# adapter.net
KiCad netlist of a schematic drawn in EAGLE
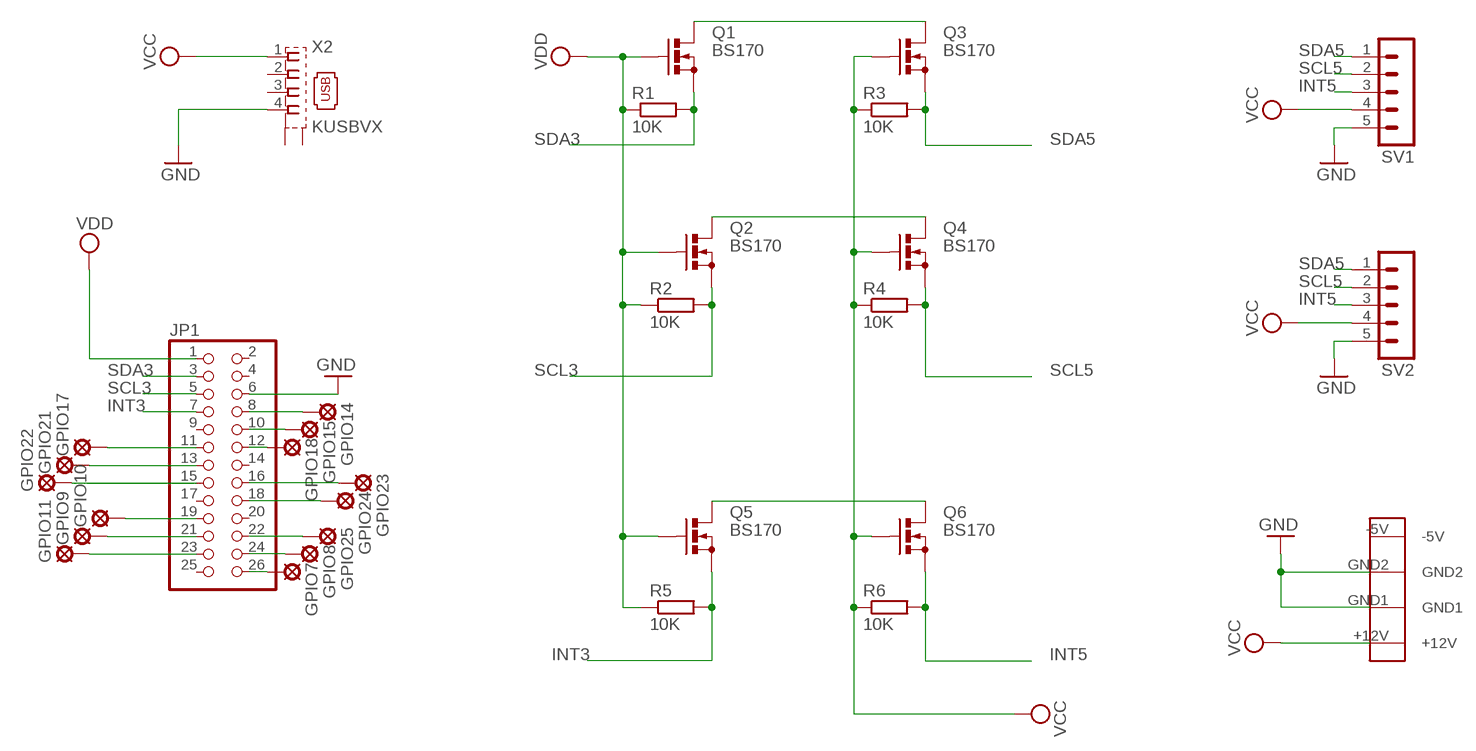
[diagram p0: schematic, sheet 1]

(export (version "E")
  (design (tool "Eeschema 10.0.6"))
  (components
    (comp (ref "GPIO7")
      (value "LSP10")
      (footprint "eagle-import:LSP10")
      (libsource (lib "eagle-import") (part "LSP10"))
    )
    (comp (ref "GPIO8")
      (value "LSP10")
      (footprint "eagle-import:LSP10")
      (libsource (lib "eagle-import") (part "LSP10"))
    )
    (comp (ref "GPIO9")
      (value "LSP10")
      (footprint "eagle-import:LSP10")
      (libsource (lib "eagle-import") (part "LSP10"))
    )
    (comp (ref "GPIO10")
      (value "LSP10")
      (footprint "eagle-import:LSP10")
      (libsource (lib "eagle-import") (part "LSP10"))
    )
    (comp (ref "GPIO11")
      (value "LSP10")
      (footprint "eagle-import:LSP10")
      (libsource (lib "eagle-import") (part "LSP10"))
    )
    (comp (ref "GPIO14")
      (value "LSP10")
      (footprint "eagle-import:LSP10")
      (libsource (lib "eagle-import") (part "LSP10"))
    )
    (comp (ref "GPIO15")
      (value "LSP10")
      (footprint "eagle-import:LSP10")
      (libsource (lib "eagle-import") (part "LSP10"))
    )
    (comp (ref "GPIO17")
      (value "GPIO17")
      (footprint "eagle-import:LSP10")
      (libsource (lib "eagle-import") (part "LSP10"))
    )
    (comp (ref "GPIO18")
      (value "LSP10")
      (footprint "eagle-import:LSP10")
      (libsource (lib "eagle-import") (part "LSP10"))
    )
    (comp (ref "GPIO21")
      (value "LSP10")
      (footprint "eagle-import:LSP10")
      (libsource (lib "eagle-import") (part "LSP10"))
    )
    (comp (ref "GPIO22")
      (value "LSP10")
      (footprint "eagle-import:LSP10")
      (libsource (lib "eagle-import") (part "LSP10"))
    )
    (comp (ref "GPIO23")
      (value "LSP10")
      (footprint "eagle-import:LSP10")
      (libsource (lib "eagle-import") (part "LSP10"))
    )
    (comp (ref "GPIO24")
      (value "LSP10")
      (footprint "eagle-import:LSP10")
      (libsource (lib "eagle-import") (part "LSP10"))
    )
    (comp (ref "GPIO25")
      (value "LSP10")
      (footprint "eagle-import:LSP10")
      (libsource (lib "eagle-import") (part "LSP10"))
    )
    (comp (ref "JP1")
      (value "PINHD-2X13")
      (footprint "eagle-import:2X13")
      (libsource (lib "eagle-import") (part "PINHD-2X13"))
    )
    (comp (ref "Q1")
      (value "BS170")
      (footprint "eagle-import:SOT54E")
      (libsource (lib "eagle-import") (part "BS170"))
    )
    (comp (ref "Q2")
      (value "BS170")
      (footprint "eagle-import:SOT54E")
      (libsource (lib "eagle-import") (part "BS170"))
    )
    (comp (ref "Q3")
      (value "BS170")
      (footprint "eagle-import:SOT54E")
      (libsource (lib "eagle-import") (part "BS170"))
    )
    (comp (ref "Q4")
      (value "BS170")
      (footprint "eagle-import:SOT54E")
      (libsource (lib "eagle-import") (part "BS170"))
    )
    (comp (ref "Q5")
      (value "BS170")
      (footprint "eagle-import:SOT54E")
      (libsource (lib "eagle-import") (part "BS170"))
    )
    (comp (ref "Q6")
      (value "BS170")
      (footprint "eagle-import:SOT54E")
      (libsource (lib "eagle-import") (part "BS170"))
    )
    (comp (ref "R1")
      (value "10K")
      (footprint "eagle-import:0207_2V")
      (libsource (lib "eagle-import") (part "R-EU_0207/2V"))
    )
    (comp (ref "R2")
      (value "10K")
      (footprint "eagle-import:0207_2V")
      (libsource (lib "eagle-import") (part "R-EU_0207/2V"))
    )
    (comp (ref "R3")
      (value "10K")
      (footprint "eagle-import:0207_2V")
      (libsource (lib "eagle-import") (part "R-EU_0207/2V"))
    )
    (comp (ref "R4")
      (value "10K")
      (footprint "eagle-import:0207_2V")
      (libsource (lib "eagle-import") (part "R-EU_0207/2V"))
    )
    (comp (ref "R5")
      (value "10K")
      (footprint "eagle-import:0207_2V")
      (libsource (lib "eagle-import") (part "R-EU_0207/2V"))
    )
    (comp (ref "R6")
      (value "10K")
      (footprint "eagle-import:0207_2V")
      (libsource (lib "eagle-import") (part "R-EU_0207/2V"))
    )
    (comp (ref "SV1")
      (value "MA05-1")
      (footprint "eagle-import:MA05-1")
      (libsource (lib "eagle-import") (part "MA05-1"))
    )
    (comp (ref "SV2")
      (value "MA05-1")
      (footprint "eagle-import:MA05-1")
      (libsource (lib "eagle-import") (part "MA05-1"))
    )
    (comp (ref "U$1")
      (value "PSW_5")
      (footprint "eagle-import:PSW_5")
      (libsource (lib "eagle-import") (part "PSW_5"))
    )
    (comp (ref "X2")
      (value "KUSBVX")
      (footprint "eagle-import:KUSBVX")
      (libsource (lib "eagle-import") (part "KUSBVX"))
    )
  )
  (nets
    (net (code "1") (name "/INT3") (class "Default")
      (node (ref "JP1") (pin "7") (pinfunction "7_7") (pintype "passive"))
      (node (ref "Q5") (pin "S") (pinfunction "S_S") (pintype "passive"))
      (node (ref "R5") (pin "2") (pinfunction "2_2") (pintype "passive"))
    )
    (net (code "2") (name "/INT5") (class "Default")
      (node (ref "Q6") (pin "S") (pinfunction "S_S") (pintype "passive"))
      (node (ref "R6") (pin "2") (pinfunction "2_2") (pintype "passive"))
      (node (ref "SV1") (pin "3") (pinfunction "3_3") (pintype "passive"))
      (node (ref "SV2") (pin "3") (pinfunction "3_3") (pintype "passive"))
    )
    (net (code "3") (name "/SCL3") (class "Default")
      (node (ref "JP1") (pin "5") (pinfunction "5_5") (pintype "passive"))
      (node (ref "Q2") (pin "S") (pinfunction "S_S") (pintype "passive"))
      (node (ref "R2") (pin "2") (pinfunction "2_2") (pintype "passive"))
    )
    (net (code "4") (name "/SCL5") (class "Default")
      (node (ref "Q4") (pin "S") (pinfunction "S_S") (pintype "passive"))
      (node (ref "R4") (pin "2") (pinfunction "2_2") (pintype "passive"))
      (node (ref "SV1") (pin "2") (pinfunction "2_2") (pintype "passive"))
      (node (ref "SV2") (pin "2") (pinfunction "2_2") (pintype "passive"))
    )
    (net (code "5") (name "/SDA3") (class "Default")
      (node (ref "JP1") (pin "3") (pinfunction "3_3") (pintype "passive"))
      (node (ref "Q1") (pin "S") (pinfunction "S_S") (pintype "passive"))
      (node (ref "R1") (pin "2") (pinfunction "2_2") (pintype "passive"))
    )
    (net (code "6") (name "/SDA5") (class "Default")
      (node (ref "Q3") (pin "S") (pinfunction "S_S") (pintype "passive"))
      (node (ref "R3") (pin "2") (pinfunction "2_2") (pintype "passive"))
      (node (ref "SV1") (pin "1") (pinfunction "1_1") (pintype "passive"))
      (node (ref "SV2") (pin "1") (pinfunction "1_1") (pintype "passive"))
    )
    (net (code "7") (name "GND") (class "Default")
      (node (ref "JP1") (pin "6") (pinfunction "6_6") (pintype "passive"))
      (node (ref "SV1") (pin "5") (pinfunction "5_5") (pintype "passive"))
      (node (ref "SV2") (pin "5") (pinfunction "5_5") (pintype "passive"))
      (node (ref "U$1") (pin "GND1") (pinfunction "GND1_GND1") (pintype "bidirectional"))
      (node (ref "U$1") (pin "GND2") (pinfunction "GND2_GND2") (pintype "bidirectional"))
      (node (ref "X2") (pin "4") (pinfunction "4_4") (pintype "passive"))
    )
    (net (code "8") (name "Net-(GPIO7-PadMP)") (class "Default")
      (node (ref "GPIO7") (pin "MP") (pinfunction "MP_MP") (pintype "passive"))
      (node (ref "JP1") (pin "26") (pinfunction "26_26") (pintype "passive"))
    )
    (net (code "9") (name "Net-(GPIO8-PadMP)") (class "Default")
      (node (ref "GPIO8") (pin "MP") (pinfunction "MP_MP") (pintype "passive"))
      (node (ref "JP1") (pin "24") (pinfunction "24_24") (pintype "passive"))
    )
    (net (code "10") (name "Net-(GPIO9-PadMP)") (class "Default")
      (node (ref "GPIO9") (pin "MP") (pinfunction "MP_MP") (pintype "passive"))
      (node (ref "JP1") (pin "21") (pinfunction "21_21") (pintype "passive"))
    )
    (net (code "11") (name "Net-(GPIO10-PadMP)") (class "Default")
      (node (ref "GPIO10") (pin "MP") (pinfunction "MP_MP") (pintype "passive"))
      (node (ref "JP1") (pin "19") (pinfunction "19_19") (pintype "passive"))
    )
    (net (code "12") (name "Net-(GPIO11-PadMP)") (class "Default")
      (node (ref "GPIO11") (pin "MP") (pinfunction "MP_MP") (pintype "passive"))
      (node (ref "JP1") (pin "23") (pinfunction "23_23") (pintype "passive"))
    )
    (net (code "13") (name "Net-(GPIO14-PadMP)") (class "Default")
      (node (ref "GPIO14") (pin "MP") (pinfunction "MP_MP") (pintype "passive"))
      (node (ref "JP1") (pin "8") (pinfunction "8_8") (pintype "passive"))
    )
    (net (code "14") (name "Net-(GPIO15-PadMP)") (class "Default")
      (node (ref "GPIO15") (pin "MP") (pinfunction "MP_MP") (pintype "passive"))
      (node (ref "JP1") (pin "10") (pinfunction "10_10") (pintype "passive"))
    )
    (net (code "15") (name "Net-(GPIO17-PadMP)") (class "Default")
      (node (ref "GPIO17") (pin "MP") (pinfunction "MP_MP") (pintype "passive"))
      (node (ref "JP1") (pin "11") (pinfunction "11_11") (pintype "passive"))
    )
    (net (code "16") (name "Net-(GPIO18-PadMP)") (class "Default")
      (node (ref "GPIO18") (pin "MP") (pinfunction "MP_MP") (pintype "passive"))
      (node (ref "JP1") (pin "12") (pinfunction "12_12") (pintype "passive"))
    )
    (net (code "17") (name "Net-(GPIO21-PadMP)") (class "Default")
      (node (ref "GPIO21") (pin "MP") (pinfunction "MP_MP") (pintype "passive"))
      (node (ref "JP1") (pin "13") (pinfunction "13_13") (pintype "passive"))
    )
    (net (code "18") (name "Net-(GPIO22-PadMP)") (class "Default")
      (node (ref "GPIO22") (pin "MP") (pinfunction "MP_MP") (pintype "passive"))
      (node (ref "JP1") (pin "15") (pinfunction "15_15") (pintype "passive"))
    )
    (net (code "19") (name "Net-(GPIO23-PadMP)") (class "Default")
      (node (ref "GPIO23") (pin "MP") (pinfunction "MP_MP") (pintype "passive"))
      (node (ref "JP1") (pin "16") (pinfunction "16_16") (pintype "passive"))
    )
    (net (code "20") (name "Net-(GPIO24-PadMP)") (class "Default")
      (node (ref "GPIO24") (pin "MP") (pinfunction "MP_MP") (pintype "passive"))
      (node (ref "JP1") (pin "18") (pinfunction "18_18") (pintype "passive"))
    )
    (net (code "21") (name "Net-(GPIO25-PadMP)") (class "Default")
      (node (ref "GPIO25") (pin "MP") (pinfunction "MP_MP") (pintype "passive"))
      (node (ref "JP1") (pin "22") (pinfunction "22_22") (pintype "passive"))
    )
    (net (code "22") (name "Net-(Q1-PadD)") (class "Default")
      (node (ref "Q1") (pin "D") (pinfunction "D_D") (pintype "passive"))
      (node (ref "Q3") (pin "D") (pinfunction "D_D") (pintype "passive"))
    )
    (net (code "23") (name "Net-(Q2-PadD)") (class "Default")
      (node (ref "Q2") (pin "D") (pinfunction "D_D") (pintype "passive"))
      (node (ref "Q4") (pin "D") (pinfunction "D_D") (pintype "passive"))
    )
    (net (code "24") (name "Net-(Q5-PadD)") (class "Default")
      (node (ref "Q5") (pin "D") (pinfunction "D_D") (pintype "passive"))
      (node (ref "Q6") (pin "D") (pinfunction "D_D") (pintype "passive"))
    )
    (net (code "25") (name "VCC") (class "Default")
      (node (ref "Q3") (pin "G") (pinfunction "G_G") (pintype "passive"))
      (node (ref "Q4") (pin "G") (pinfunction "G_G") (pintype "passive"))
      (node (ref "Q6") (pin "G") (pinfunction "G_G") (pintype "passive"))
      (node (ref "R3") (pin "1") (pinfunction "1_1") (pintype "passive"))
      (node (ref "R4") (pin "1") (pinfunction "1_1") (pintype "passive"))
      (node (ref "R6") (pin "1") (pinfunction "1_1") (pintype "passive"))
      (node (ref "SV1") (pin "4") (pinfunction "4_4") (pintype "passive"))
      (node (ref "SV2") (pin "4") (pinfunction "4_4") (pintype "passive"))
      (node (ref "U$1") (pin "+12V") (pinfunction "+12V_+12V") (pintype "bidirectional"))
      (node (ref "X2") (pin "1") (pinfunction "1_1") (pintype "passive"))
    )
    (net (code "26") (name "VDD") (class "Default")
      (node (ref "JP1") (pin "1") (pinfunction "1_1") (pintype "passive"))
      (node (ref "Q1") (pin "G") (pinfunction "G_G") (pintype "passive"))
      (node (ref "Q2") (pin "G") (pinfunction "G_G") (pintype "passive"))
      (node (ref "Q5") (pin "G") (pinfunction "G_G") (pintype "passive"))
      (node (ref "R1") (pin "1") (pinfunction "1_1") (pintype "passive"))
      (node (ref "R2") (pin "1") (pinfunction "1_1") (pintype "passive"))
      (node (ref "R5") (pin "1") (pinfunction "1_1") (pintype "passive"))
    )
    (net (code "27") (name "unconnected-(JP1-Pad2)") (class "Default")
      (node (ref "JP1") (pin "2") (pinfunction "2_2") (pintype "passive"))
    )
    (net (code "28") (name "unconnected-(JP1-Pad4)") (class "Default")
      (node (ref "JP1") (pin "4") (pinfunction "4_4") (pintype "passive"))
    )
    (net (code "29") (name "unconnected-(JP1-Pad9)") (class "Default")
      (node (ref "JP1") (pin "9") (pinfunction "9_9") (pintype "passive"))
    )
    (net (code "30") (name "unconnected-(JP1-Pad14)") (class "Default")
      (node (ref "JP1") (pin "14") (pinfunction "14_14") (pintype "passive"))
    )
    (net (code "31") (name "unconnected-(JP1-Pad17)") (class "Default")
      (node (ref "JP1") (pin "17") (pinfunction "17_17") (pintype "passive"))
    )
    (net (code "32") (name "unconnected-(JP1-Pad20)") (class "Default")
      (node (ref "JP1") (pin "20") (pinfunction "20_20") (pintype "passive"))
    )
    (net (code "33") (name "unconnected-(JP1-Pad25)") (class "Default")
      (node (ref "JP1") (pin "25") (pinfunction "25_25") (pintype "passive"))
    )
    (net (code "34") (name "unconnected-(U$1-Pad-5V)") (class "Default")
      (node (ref "U$1") (pin "-5V") (pinfunction "-5V_-5V") (pintype "bidirectional"))
    )
    (net (code "35") (name "unconnected-(X2-Pad2)") (class "Default")
      (node (ref "X2") (pin "2") (pinfunction "2_2") (pintype "passive"))
    )
    (net (code "36") (name "unconnected-(X2-Pad3)") (class "Default")
      (node (ref "X2") (pin "3") (pinfunction "3_3") (pintype "passive"))
    )
    (net (code "37") (name "unconnected-(X2-S1-PadM1)") (class "Default")
      (node (ref "X2") (pin "M1") (pinfunction "S1_M1") (pintype "passive"))
    )
    (net (code "38") (name "unconnected-(X2-S2-PadM2)") (class "Default")
      (node (ref "X2") (pin "M2") (pinfunction "S2_M2") (pintype "passive"))
    )
  )
)
